# GLCD.net
KiCad netlist of a schematic drawn in Altium Designer
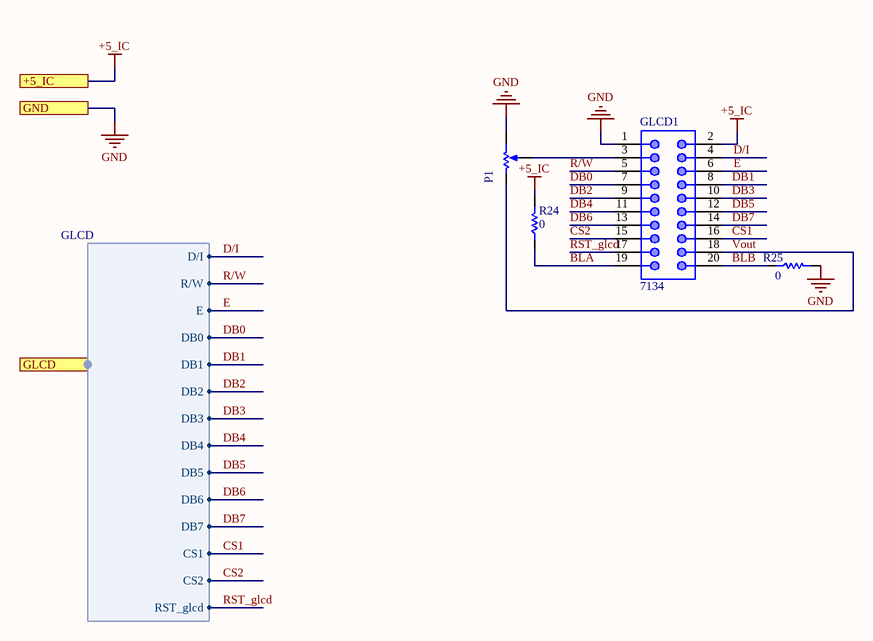
[diagram p0: GLCD.SchDoc]

(export (version "E")
  (design (tool "Eeschema 10.0.6"))
  (components
    (comp (ref "GLCD1")
      (value "10x2")
      (footprint "BOX-HDR-10X2-2.54mm-S")
      (description "Male Box Header, 20 pins")
      (fields (field (name "INFLOW") "7134") (field (name "VALIDATION") "NT"))
      (libsource (lib "aKaReZa") (part "Con_IDC_10x2"))
    )
    (comp (ref "P1")
      (value "10K")
      (footprint "Multi turn 01")
      (description "Multi Turn")
      (fields (field (name "VALIDATION") "Valid"))
      (libsource (lib "aKaReZa") (part "Res_Multi"))
    )
    (comp (ref "R24")
      (value "0")
      (footprint "RES 1206 (3216X08L)")
      (description "Resistor")
      (fields (field (name "VALIDATION") "Valid"))
      (libsource (lib "aKaReZa") (part "Res_SMD_1206"))
    )
    (comp (ref "R25")
      (value "0")
      (footprint "RES 1206 (3216X08L)")
      (description "Resistor")
      (fields (field (name "VALIDATION") "Valid"))
      (libsource (lib "aKaReZa") (part "Res_SMD_1206"))
    )
  )
  (nets
    (net (code "2") (name "+5_IC") (class "Default")
      (node (ref "GLCD1") (pin "2") (pinfunction "2_2") (pintype "passive"))
      (node (ref "R24") (pin "2") (pinfunction "2_2") (pintype "passive"))
    )
    (net (code "3") (name "/BLA") (class "Default")
      (node (ref "GLCD1") (pin "19") (pinfunction "19_19") (pintype "passive"))
      (node (ref "R24") (pin "1") (pinfunction "1_1") (pintype "passive"))
    )
    (net (code "4") (name "/BLB") (class "Default")
      (node (ref "GLCD1") (pin "20") (pinfunction "20_20") (pintype "passive"))
      (node (ref "R25") (pin "1") (pinfunction "1_1") (pintype "passive"))
    )
    (net (code "5") (name "/CS1") (class "Default")
      (node (ref "GLCD1") (pin "16") (pinfunction "16_16") (pintype "passive"))
    )
    (net (code "6") (name "/CS2") (class "Default")
      (node (ref "GLCD1") (pin "15") (pinfunction "15_15") (pintype "passive"))
    )
    (net (code "7") (name "/DB0") (class "Default")
      (node (ref "GLCD1") (pin "7") (pinfunction "7_7") (pintype "passive"))
    )
    (net (code "8") (name "/DB1") (class "Default")
      (node (ref "GLCD1") (pin "8") (pinfunction "8_8") (pintype "passive"))
    )
    (net (code "9") (name "/DB2") (class "Default")
      (node (ref "GLCD1") (pin "9") (pinfunction "9_9") (pintype "passive"))
    )
    (net (code "10") (name "/DB3") (class "Default")
      (node (ref "GLCD1") (pin "10") (pinfunction "10_10") (pintype "passive"))
    )
    (net (code "11") (name "/DB4") (class "Default")
      (node (ref "GLCD1") (pin "11") (pinfunction "11_11") (pintype "passive"))
    )
    (net (code "12") (name "/DB5") (class "Default")
      (node (ref "GLCD1") (pin "12") (pinfunction "12_12") (pintype "passive"))
    )
    (net (code "13") (name "/DB6") (class "Default")
      (node (ref "GLCD1") (pin "13") (pinfunction "13_13") (pintype "passive"))
    )
    (net (code "14") (name "/DB7") (class "Default")
      (node (ref "GLCD1") (pin "14") (pinfunction "14_14") (pintype "passive"))
    )
    (net (code "15") (name "/D{slash}I") (class "Default")
      (node (ref "GLCD1") (pin "4") (pinfunction "4_4") (pintype "passive"))
    )
    (net (code "16") (name "/E") (class "Default")
      (node (ref "GLCD1") (pin "6") (pinfunction "6_6") (pintype "passive"))
    )
    (net (code "17") (name "/RST_glcd") (class "Default")
      (node (ref "GLCD1") (pin "17") (pinfunction "17_17") (pintype "passive"))
    )
    (net (code "18") (name "/R{slash}W") (class "Default")
      (node (ref "GLCD1") (pin "5") (pinfunction "5_5") (pintype "passive"))
    )
    (net (code "19") (name "/Vout") (class "Default")
      (node (ref "GLCD1") (pin "18") (pinfunction "18_18") (pintype "passive"))
      (node (ref "P1") (pin "3") (pinfunction "1_3") (pintype "passive"))
    )
    (net (code "21") (name "GND") (class "Default")
      (node (ref "GLCD1") (pin "1") (pinfunction "1_1") (pintype "passive"))
      (node (ref "P1") (pin "1") (pinfunction "3_1") (pintype "passive"))
      (node (ref "R25") (pin "2") (pinfunction "2_2") (pintype "passive"))
    )
    (net (code "22") (name "Net-(GLCD1-Pad3)") (class "Default")
      (node (ref "GLCD1") (pin "3") (pinfunction "3_3") (pintype "passive"))
      (node (ref "P1") (pin "2") (pinfunction "2_2") (pintype "passive"))
    )
  )
)
